# AMC-SATA.net
KiCad netlist of a schematic drawn in Altium Designer
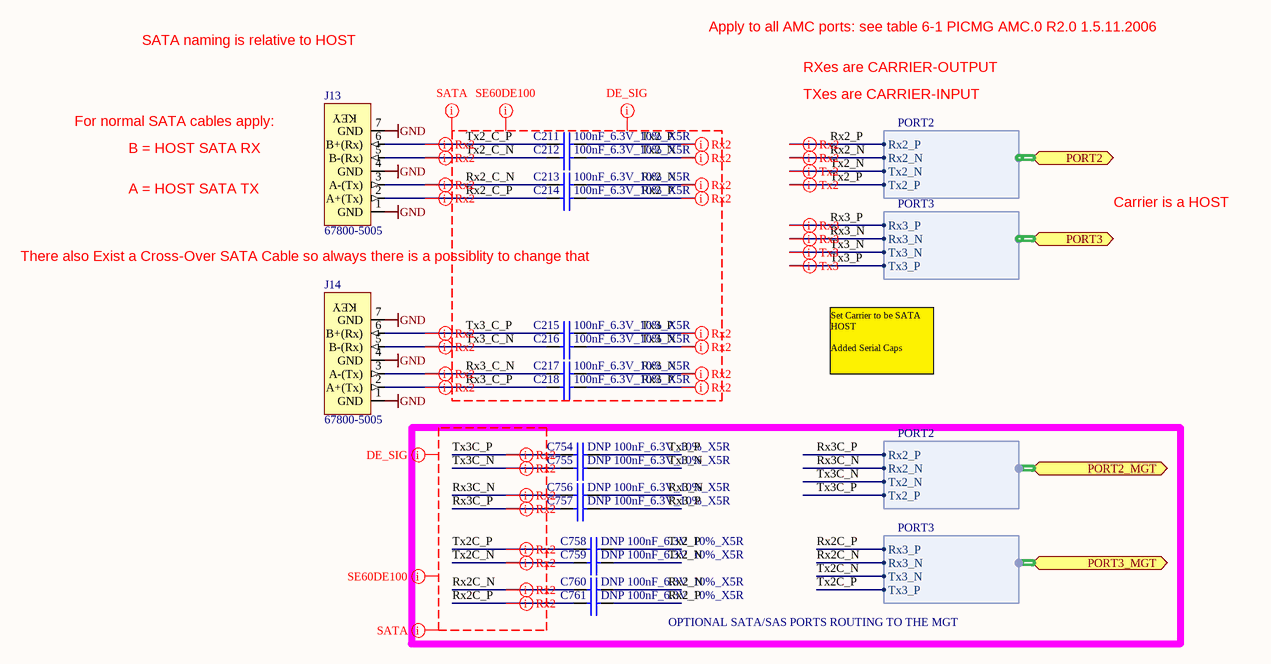
[diagram p0: AMC-SATA.SchDoc]

(export (version "E")
  (design (tool "Eeschema 10.0.6"))
  (components
    (comp (ref "C211")
      (value "100nF_6.3V_10%_X5R")
      (footprint "0201C")
      (description "Capacitor SMD")
      (libsource (lib "LIBRARY_SCH") (part "CAP_SMD_0201"))
    )
    (comp (ref "C212")
      (value "100nF_6.3V_10%_X5R")
      (footprint "0201C")
      (description "Capacitor SMD")
      (libsource (lib "LIBRARY_SCH") (part "CAP_SMD_0201"))
    )
    (comp (ref "C213")
      (value "100nF_6.3V_10%_X5R")
      (footprint "0201C")
      (description "Capacitor SMD")
      (libsource (lib "LIBRARY_SCH") (part "CAP_SMD_0201"))
    )
    (comp (ref "C214")
      (value "100nF_6.3V_10%_X5R")
      (footprint "0201C")
      (description "Capacitor SMD")
      (libsource (lib "LIBRARY_SCH") (part "CAP_SMD_0201"))
    )
    (comp (ref "C215")
      (value "100nF_6.3V_10%_X5R")
      (footprint "0201C")
      (description "Capacitor SMD")
      (libsource (lib "LIBRARY_SCH") (part "CAP_SMD_0201"))
    )
    (comp (ref "C216")
      (value "100nF_6.3V_10%_X5R")
      (footprint "0201C")
      (description "Capacitor SMD")
      (libsource (lib "LIBRARY_SCH") (part "CAP_SMD_0201"))
    )
    (comp (ref "C217")
      (value "100nF_6.3V_10%_X5R")
      (footprint "0201C")
      (description "Capacitor SMD")
      (libsource (lib "LIBRARY_SCH") (part "CAP_SMD_0201"))
    )
    (comp (ref "C218")
      (value "100nF_6.3V_10%_X5R")
      (footprint "0201C")
      (description "Capacitor SMD")
      (libsource (lib "LIBRARY_SCH") (part "CAP_SMD_0201"))
    )
    (comp (ref "C754")
      (value "DNP 100nF_6.3V_10%_X5R")
      (footprint "0201C")
      (description "Capacitor SMD")
      (libsource (lib "LIBRARY_SCH") (part "CAP_SMD_0201"))
    )
    (comp (ref "C755")
      (value "DNP 100nF_6.3V_10%_X5R")
      (footprint "0201C")
      (description "Capacitor SMD")
      (libsource (lib "LIBRARY_SCH") (part "CAP_SMD_0201"))
    )
    (comp (ref "C756")
      (value "DNP 100nF_6.3V_10%_X5R")
      (footprint "0201C")
      (description "Capacitor SMD")
      (libsource (lib "LIBRARY_SCH") (part "CAP_SMD_0201"))
    )
    (comp (ref "C757")
      (value "DNP 100nF_6.3V_10%_X5R")
      (footprint "0201C")
      (description "Capacitor SMD")
      (libsource (lib "LIBRARY_SCH") (part "CAP_SMD_0201"))
    )
    (comp (ref "C758")
      (value "DNP 100nF_6.3V_10%_X5R")
      (footprint "0201C")
      (description "Capacitor SMD")
      (libsource (lib "LIBRARY_SCH") (part "CAP_SMD_0201"))
    )
    (comp (ref "C759")
      (value "DNP 100nF_6.3V_10%_X5R")
      (footprint "0201C")
      (description "Capacitor SMD")
      (libsource (lib "LIBRARY_SCH") (part "CAP_SMD_0201"))
    )
    (comp (ref "C760")
      (value "DNP 100nF_6.3V_10%_X5R")
      (footprint "0201C")
      (description "Capacitor SMD")
      (libsource (lib "LIBRARY_SCH") (part "CAP_SMD_0201"))
    )
    (comp (ref "C761")
      (value "DNP 100nF_6.3V_10%_X5R")
      (footprint "0201C")
      (description "Capacitor SMD")
      (libsource (lib "LIBRARY_SCH") (part "CAP_SMD_0201"))
    )
    (comp (ref "J13")
      (value "67800-5005")
      (footprint "CON_SATA_V")
      (description "SATA conenctor  PCB Molex")
      (libsource (lib "AMC_FMC_Carrier") (part "CON_SATA_V"))
    )
    (comp (ref "J14")
      (value "67800-5005")
      (footprint "CON_SATA_V")
      (description "SATA conenctor  PCB Molex")
      (libsource (lib "AMC_FMC_Carrier") (part "CON_SATA_V"))
    )
  )
  (nets
    (net (code "3") (name "/Rx2C_N") (class "Default")
      (node (ref "C760") (pin "1") (pinfunction "1_1") (pintype "passive"))
    )
    (net (code "4") (name "/Rx2C_P") (class "Default")
      (node (ref "C761") (pin "1") (pinfunction "1_1") (pintype "passive"))
    )
    (net (code "5") (name "/Rx2_C_N") (class "Default")
      (node (ref "C213") (pin "1") (pinfunction "1_1") (pintype "passive"))
      (node (ref "J13") (pin "3") (pinfunction "A-(Tx)_3") (pintype "output"))
    )
    (net (code "6") (name "/Rx2_C_P") (class "Default")
      (node (ref "C214") (pin "1") (pinfunction "1_1") (pintype "passive"))
      (node (ref "J13") (pin "2") (pinfunction "A+(Tx)_2") (pintype "output"))
    )
    (net (code "7") (name "/Rx2_N") (class "Default")
      (node (ref "C213") (pin "2") (pinfunction "2_2") (pintype "passive"))
      (node (ref "C760") (pin "2") (pinfunction "2_2") (pintype "passive"))
    )
    (net (code "8") (name "/Rx2_P") (class "Default")
      (node (ref "C214") (pin "2") (pinfunction "2_2") (pintype "passive"))
      (node (ref "C761") (pin "2") (pinfunction "2_2") (pintype "passive"))
    )
    (net (code "9") (name "/Rx3C_N") (class "Default")
      (node (ref "C756") (pin "1") (pinfunction "1_1") (pintype "passive"))
    )
    (net (code "10") (name "/Rx3C_P") (class "Default")
      (node (ref "C757") (pin "1") (pinfunction "1_1") (pintype "passive"))
    )
    (net (code "11") (name "/Rx3_C_N") (class "Default")
      (node (ref "C217") (pin "1") (pinfunction "1_1") (pintype "passive"))
      (node (ref "J14") (pin "3") (pinfunction "A-(Tx)_3") (pintype "output"))
    )
    (net (code "12") (name "/Rx3_C_P") (class "Default")
      (node (ref "C218") (pin "1") (pinfunction "1_1") (pintype "passive"))
      (node (ref "J14") (pin "2") (pinfunction "A+(Tx)_2") (pintype "output"))
    )
    (net (code "13") (name "/Rx3_N") (class "Default")
      (node (ref "C217") (pin "2") (pinfunction "2_2") (pintype "passive"))
      (node (ref "C756") (pin "2") (pinfunction "2_2") (pintype "passive"))
    )
    (net (code "14") (name "/Rx3_P") (class "Default")
      (node (ref "C218") (pin "2") (pinfunction "2_2") (pintype "passive"))
      (node (ref "C757") (pin "2") (pinfunction "2_2") (pintype "passive"))
    )
    (net (code "15") (name "/Tx2C_N") (class "Default")
      (node (ref "C759") (pin "1") (pinfunction "1_1") (pintype "passive"))
    )
    (net (code "16") (name "/Tx2C_P") (class "Default")
      (node (ref "C758") (pin "1") (pinfunction "1_1") (pintype "passive"))
    )
    (net (code "17") (name "/Tx2_C_N") (class "Default")
      (node (ref "C212") (pin "1") (pinfunction "1_1") (pintype "passive"))
      (node (ref "J13") (pin "5") (pinfunction "B-(Rx)_5") (pintype "input"))
    )
    (net (code "18") (name "/Tx2_C_P") (class "Default")
      (node (ref "C211") (pin "1") (pinfunction "1_1") (pintype "passive"))
      (node (ref "J13") (pin "6") (pinfunction "B+(Rx)_6") (pintype "input"))
    )
    (net (code "19") (name "/Tx2_N") (class "Default")
      (node (ref "C212") (pin "2") (pinfunction "2_2") (pintype "passive"))
      (node (ref "C759") (pin "2") (pinfunction "2_2") (pintype "passive"))
    )
    (net (code "20") (name "/Tx2_P") (class "Default")
      (node (ref "C211") (pin "2") (pinfunction "2_2") (pintype "passive"))
      (node (ref "C758") (pin "2") (pinfunction "2_2") (pintype "passive"))
    )
    (net (code "21") (name "/Tx3C_N") (class "Default")
      (node (ref "C755") (pin "1") (pinfunction "1_1") (pintype "passive"))
    )
    (net (code "22") (name "/Tx3C_P") (class "Default")
      (node (ref "C754") (pin "1") (pinfunction "1_1") (pintype "passive"))
    )
    (net (code "23") (name "/Tx3_C_N") (class "Default")
      (node (ref "C216") (pin "1") (pinfunction "1_1") (pintype "passive"))
      (node (ref "J14") (pin "5") (pinfunction "B-(Rx)_5") (pintype "input"))
    )
    (net (code "24") (name "/Tx3_C_P") (class "Default")
      (node (ref "C215") (pin "1") (pinfunction "1_1") (pintype "passive"))
      (node (ref "J14") (pin "6") (pinfunction "B+(Rx)_6") (pintype "input"))
    )
    (net (code "25") (name "/Tx3_N") (class "Default")
      (node (ref "C216") (pin "2") (pinfunction "2_2") (pintype "passive"))
      (node (ref "C755") (pin "2") (pinfunction "2_2") (pintype "passive"))
    )
    (net (code "26") (name "/Tx3_P") (class "Default")
      (node (ref "C215") (pin "2") (pinfunction "2_2") (pintype "passive"))
      (node (ref "C754") (pin "2") (pinfunction "2_2") (pintype "passive"))
    )
    (net (code "29") (name "GND") (class "Default")
      (node (ref "J13") (pin "1") (pinfunction "GND_1") (pintype "power_in"))
      (node (ref "J13") (pin "4") (pinfunction "GND_4") (pintype "power_in"))
      (node (ref "J13") (pin "7") (pinfunction "GND_7") (pintype "power_in"))
      (node (ref "J14") (pin "1") (pinfunction "GND_1") (pintype "power_in"))
      (node (ref "J14") (pin "4") (pinfunction "GND_4") (pintype "power_in"))
      (node (ref "J14") (pin "7") (pinfunction "GND_7") (pintype "power_in"))
    )
  )
)
